# thingy.net
KiCad netlist of a schematic drawn in EAGLE
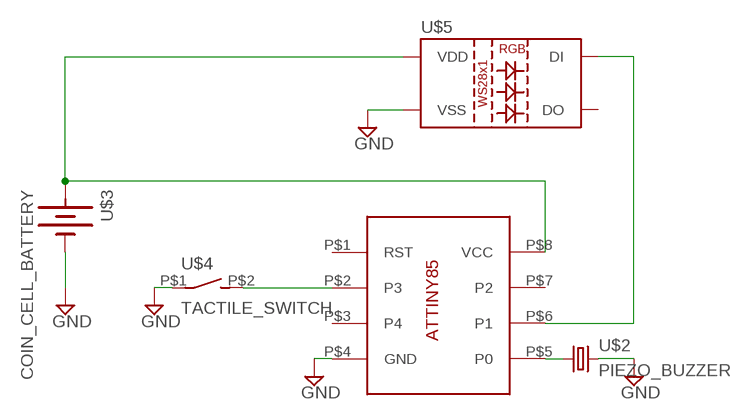
[diagram p0: schematic, sheet 1]

(export (version "E")
  (design (tool "Eeschema 10.0.6"))
  (components
    (comp (ref "U$1")
      (value "ATTINY85-SOCKET")
      (footprint "eagle-import:DIP8SOCKET")
      (libsource (lib "eagle-import") (part "ATTINY85-SOCKET"))
    )
    (comp (ref "U$2")
      (value "PIEZO_BUZZER")
      (footprint "eagle-import:PIEZO_BUZZER")
      (libsource (lib "eagle-import") (part "PIEZO_BUZZER"))
    )
    (comp (ref "U$3")
      (value "COIN_CELL_BATTERY")
      (footprint "eagle-import:COIN_BATTERY")
      (libsource (lib "eagle-import") (part "COIN_CELL_BATTERY"))
    )
    (comp (ref "U$4")
      (value "TACTILE_SWITCH")
      (footprint "eagle-import:TACTILE_SWITCH")
      (libsource (lib "eagle-import") (part "TACTILE_SWITCH"))
    )
    (comp (ref "U$5")
      (value "5MM-NEOPIXEL")
      (footprint "eagle-import:T1-3_4-LED")
      (libsource (lib "eagle-import") (part "5MM-NEOPIXEL"))
    )
  )
  (nets
    (net (code "1") (name "GND") (class "Default")
      (node (ref "U$1") (pin "P$4") (pinfunction "GND_P$4") (pintype "bidirectional"))
      (node (ref "U$2") (pin "P$2") (pinfunction "2_P$2") (pintype "passive"))
      (node (ref "U$3") (pin "P$2") (pinfunction "-_P$2") (pintype "power_in"))
      (node (ref "U$4") (pin "P$1") (pinfunction "P_P$1") (pintype "passive"))
      (node (ref "U$5") (pin "P$3") (pinfunction "VSS_P$3") (pintype "bidirectional"))
    )
    (net (code "2") (name "Net-(U$1-P0)") (class "Default")
      (node (ref "U$1") (pin "P$5") (pinfunction "P0_P$5") (pintype "bidirectional"))
      (node (ref "U$2") (pin "P$1") (pinfunction "1_P$1") (pintype "passive"))
    )
    (net (code "3") (name "Net-(U$1-P1)") (class "Default")
      (node (ref "U$1") (pin "P$6") (pinfunction "P1_P$6") (pintype "bidirectional"))
      (node (ref "U$5") (pin "P$1") (pinfunction "DI_P$1") (pintype "bidirectional"))
    )
    (net (code "4") (name "Net-(U$1-P3)") (class "Default")
      (node (ref "U$1") (pin "P$2") (pinfunction "P3_P$2") (pintype "bidirectional"))
      (node (ref "U$4") (pin "P$2") (pinfunction "S_P$2") (pintype "passive"))
    )
    (net (code "5") (name "Net-(U$1-VCC)") (class "Default")
      (node (ref "U$1") (pin "P$8") (pinfunction "VCC_P$8") (pintype "bidirectional"))
      (node (ref "U$3") (pin "P$1") (pinfunction "+_P$1") (pintype "power_in"))
      (node (ref "U$5") (pin "P$2") (pinfunction "VDD_P$2") (pintype "bidirectional"))
    )
    (net (code "6") (name "unconnected-(U$1-P2-PadP$7)") (class "Default")
      (node (ref "U$1") (pin "P$7") (pinfunction "P2_P$7") (pintype "bidirectional"))
    )
    (net (code "7") (name "unconnected-(U$1-P4-PadP$3)") (class "Default")
      (node (ref "U$1") (pin "P$3") (pinfunction "P4_P$3") (pintype "bidirectional"))
    )
    (net (code "8") (name "unconnected-(U$1-RST-PadP$1)") (class "Default")
      (node (ref "U$1") (pin "P$1") (pinfunction "RST_P$1") (pintype "bidirectional"))
    )
    (net (code "9") (name "unconnected-(U$5-DO-PadP$4)") (class "Default")
      (node (ref "U$5") (pin "P$4") (pinfunction "DO_P$4") (pintype "bidirectional"))
    )
  )
)
